# CPU.net
KiCad netlist of a schematic drawn in Altium Designer
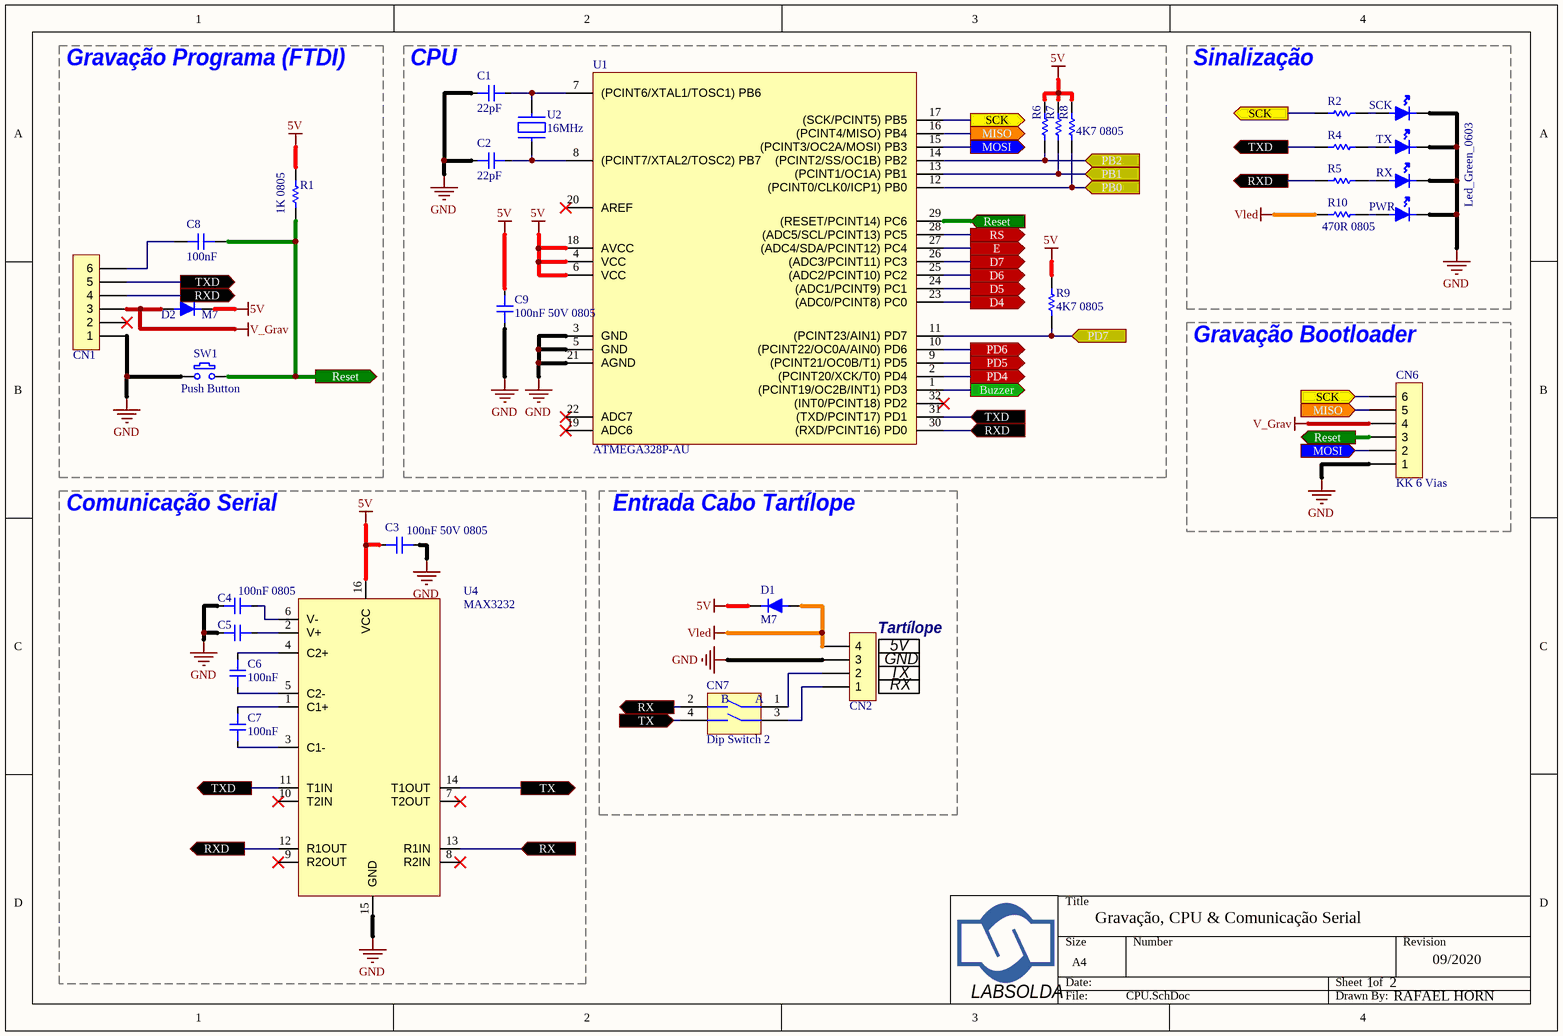
[diagram p0: CPU.SchDoc]

(export (version "E")
  (design (tool "Eeschema 10.0.6"))
  (components
    (comp (ref "C1")
      (value "22pF")
      (footprint "100nF 0805")
      (description "Capacitor 0805 100nF 16V")
      (libsource (lib "Capacitor_SMD") (part "100nF 16V 0805"))
    )
    (comp (ref "C2")
      (value "22pF")
      (footprint "100nF 0805")
      (description "Capacitor 0805 100nF 16V")
      (libsource (lib "Capacitor_SMD") (part "100nF 16V 0805"))
    )
    (comp (ref "C3")
      (value "100nF 50V 0805")
      (footprint "100nF 0805")
      (description "Capacitor 0805 100nF 16V")
      (libsource (lib "Capacitor_SMD") (part "100nF 16V 0805"))
    )
    (comp (ref "C4")
      (value "100nF 50V 0805")
      (footprint "100nF 0805")
      (description "Capacitor 0805 100nF 16V")
      (libsource (lib "Capacitor_SMD") (part "100nF 16V 0805"))
    )
    (comp (ref "C5")
      (value "100nF 0805")
      (footprint "100nF 0805")
      (description "Capacitor 0805 100nF 16V")
      (libsource (lib "Capacitor_SMD") (part "100nF 16V 0805"))
    )
    (comp (ref "C6")
      (value "100nF")
      (footprint "100nF 0805")
      (description "Capacitor 0805 100nF 16V")
      (libsource (lib "Capacitor_SMD") (part "100nF 16V 0805"))
    )
    (comp (ref "C7")
      (value "100nF")
      (footprint "100nF 0805")
      (description "Capacitor 0805 100nF 16V")
      (libsource (lib "Capacitor_SMD") (part "100nF 16V 0805"))
    )
    (comp (ref "C8")
      (value "100nF")
      (footprint "5mm film")
      (description "FILM CAPACITORS 100nF 63V")
      (libsource (lib "Capacitors_PTH") (part "100nF 63V"))
    )
    (comp (ref "C9")
      (value "100nF 50V 0805")
      (footprint "100nF 0805")
      (description "Capacitor 0805 100nF 16V")
      (libsource (lib "Capacitor_SMD") (part "100nF 16V 0805"))
    )
    (comp (ref "CN1")
      (value "Barra Pinos M")
      (footprint "Barra Pino M 6")
      (description "Barra Pino Macho 6 Vias 2.54mm")
      (libsource (lib "Conectores") (part "Barra Pino M 6"))
    )
    (comp (ref "CN2")
      (value "STLZ 4 Vias")
      (footprint "STLZ 4 5.08mm")
      (description "Conector Socket STLZ 4 Vias 5.08mm")
      (libsource (lib "Conectores") (part "STLZ 4 Vias"))
    )
    (comp (ref "CN6")
      (value "KK 6 Vias")
      (footprint "KK_6W_.100")
      (description "Conector Placa KK 6 Vias 2.54mm")
      (libsource (lib "Conectores") (part "KK 6 Vias"))
    )
    (comp (ref "CN7")
      (value "Dip Switch 2")
      (footprint "DIP_SWITCH_2")
      (description "DIP Switches / SIP Switches Dip switch Slide Type")
      (fields (field (name "PARTNUMBER") "NDSR-02V") (field (name "MANUFACTURER") "Diptronics"))
      (libsource (lib "Contatos") (part "Dip Switch 2 Vias"))
    )
    (comp (ref "D1")
      (value "M7")
      (footprint "DO-214AC SMA")
      (description "1A Rectifier Diodes")
      (libsource (lib "Diodo_SMD") (part "M7"))
    )
    (comp (ref "D2")
      (value "M7")
      (footprint "DO-214AC SMA")
      (description "1A Rectifier Diodes")
      (libsource (lib "Diodo_SMD") (part "M7"))
    )
    (comp (ref "PWR")
      (value "Green_0603")
      (footprint "Green Led 0603")
      (description "LED GREEN CLEAR 0603 SMD PN 150060VS75000")
      (libsource (lib "Leds_Lib") (part "Green 0603"))
    )
    (comp (ref "R1")
      (value "1K 0805")
      (footprint "0805 - 1K 1%")
      (description "Resistor SMD 0805 1K")
      (libsource (lib "Resistor_SMD") (part "1K - 0805"))
    )
    (comp (ref "R2")
      (value "470R 0805")
      (footprint "0805 - 470R 1%")
      (description "Resistor SMD 0805 470R")
      (libsource (lib "Resistor_SMD") (part "470R - 0805"))
    )
    (comp (ref "R4")
      (value "470R 0805")
      (footprint "0805 - 470R 1%")
      (description "Resistor SMD 0805 470R")
      (libsource (lib "Resistor_SMD") (part "470R - 0805"))
    )
    (comp (ref "R5")
      (value "470R 0805")
      (footprint "0805 - 470R 1%")
      (description "Resistor SMD 0805 470R")
      (libsource (lib "Resistor_SMD") (part "470R - 0805"))
    )
    (comp (ref "R6")
      (value "4K7")
      (footprint "0805 - 2k7 1%")
      (description "Resistor SMD 0805 2K7")
      (libsource (lib "Resistor_SMD") (part "2K7 - 0805"))
    )
    (comp (ref "R7")
      (value "4K7")
      (footprint "0805 - 2k7 1%")
      (description "Resistor SMD 0805 2K7")
      (libsource (lib "Resistor_SMD") (part "2K7 - 0805"))
    )
    (comp (ref "R8")
      (value "4K7 0805")
      (footprint "0805 - 2k7 1%")
      (description "Resistor SMD 0805 2K7")
      (libsource (lib "Resistor_SMD") (part "2K7 - 0805"))
    )
    (comp (ref "R9")
      (value "4K7 0805")
      (footprint "0805 - 2k7 1%")
      (description "Resistor SMD 0805 2K7")
      (libsource (lib "Resistor_SMD") (part "2K7 - 0805"))
    )
    (comp (ref "R10")
      (value "470R 0805")
      (footprint "0805 - 470R 1%")
      (description "Resistor SMD 0805 470R")
      (libsource (lib "Resistor_SMD") (part "470R - 0805"))
    )
    (comp (ref "RX")
      (value "Green_0603")
      (footprint "Green Led 0603")
      (description "LED GREEN CLEAR 0603 SMD PN 150060VS75000")
      (libsource (lib "Leds_Lib") (part "Green 0603"))
    )
    (comp (ref "SCK")
      (value "Led_Green_0603")
      (footprint "Green Led 0603")
      (description "LED GREEN CLEAR 0603 SMD PN 150060VS75000")
      (libsource (lib "Leds_Lib") (part "Green 0603"))
    )
    (comp (ref "SW1")
      (value "Push Button")
      (footprint "Chave Tactil 6x6x5")
      (description "Chave Tactil 4 terminais 6x6x5mm - KFC-A06")
      (libsource (lib "Contatos") (part "Push Button"))
    )
    (comp (ref "TX")
      (value "Green_0603")
      (footprint "Green Led 0603")
      (description "LED GREEN CLEAR 0603 SMD PN 150060VS75000")
      (libsource (lib "Leds_Lib") (part "Green 0603"))
    )
    (comp (ref "U1")
      (value "ATMEGA328P-AU")
      (footprint "LQFP-32")
      (description "8-bit AVR Microcontroller with 32K Bytes In-System  Programmable Flash")
      (libsource (lib "CI's") (part "ATMEGA328P"))
    )
    (comp (ref "U2")
      (value "16MHz")
      (footprint "HC49")
      (description "16MHZ OSCILATOR CRYSTAL")
      (libsource (lib "CI's") (part "Crystal 16MHz"))
    )
    (comp (ref "U4")
      (value "MAX3232")
      (footprint "DIP16-300(100)")
      (description "MAX3232 3-V to 5.5-V Multichannel RS-232 Line Driver/Receiver  With ±15-kV ESD Protection")
      (libsource (lib "CI's") (part "MAX3232"))
    )
  )
  (nets
    (net (code "1") (name "/Buzzer") (class "Default")
      (node (ref "U1") (pin "1") (pinfunction "(PCINT19/OC2B/INT1)_PD3_1") (pintype "passive"))
    )
    (net (code "2") (name "/D4") (class "Default")
      (node (ref "U1") (pin "23") (pinfunction "(ADC0/PCINT8)_PC0_23") (pintype "passive"))
    )
    (net (code "3") (name "/D5") (class "Default")
      (node (ref "U1") (pin "24") (pinfunction "(ADC1/PCINT9)_PC1_24") (pintype "passive"))
    )
    (net (code "4") (name "/D6") (class "Default")
      (node (ref "U1") (pin "25") (pinfunction "(ADC2/PCINT10)_PC2_25") (pintype "passive"))
    )
    (net (code "5") (name "/D7") (class "Default")
      (node (ref "U1") (pin "26") (pinfunction "(ADC3/PCINT11)_PC3_26") (pintype "passive"))
    )
    (net (code "6") (name "/E") (class "Default")
      (node (ref "U1") (pin "27") (pinfunction "(ADC4/SDA/PCINT12)_PC4_27") (pintype "passive"))
    )
    (net (code "7") (name "/MISO") (class "Default")
      (node (ref "CN6") (pin "5") (pinfunction "5_5") (pintype "passive"))
      (node (ref "U1") (pin "16") (pinfunction "(PCINT4/MISO)_PB4_16") (pintype "passive"))
    )
    (net (code "8") (name "/MOSI") (class "Default")
      (node (ref "CN6") (pin "2") (pinfunction "2_2") (pintype "passive"))
      (node (ref "U1") (pin "15") (pinfunction "(PCINT3/OC2A/MOSI)_PB3_15") (pintype "passive"))
    )
    (net (code "9") (name "/PB0") (class "Default")
      (node (ref "R8") (pin "1") (pinfunction "1_1") (pintype "passive"))
      (node (ref "U1") (pin "12") (pinfunction "(PCINT0/CLK0/ICP1)_PB0_12") (pintype "passive"))
    )
    (net (code "10") (name "/PB1") (class "Default")
      (node (ref "R7") (pin "1") (pinfunction "1_1") (pintype "passive"))
      (node (ref "U1") (pin "13") (pinfunction "(PCINT1/OC1A)_PB1_13") (pintype "passive"))
    )
    (net (code "11") (name "/PB2") (class "Default")
      (node (ref "R6") (pin "1") (pinfunction "1_1") (pintype "passive"))
      (node (ref "U1") (pin "14") (pinfunction "(PCINT2/SS/OC1B)_PB2_14") (pintype "passive"))
    )
    (net (code "12") (name "/PD4") (class "Default")
      (node (ref "U1") (pin "2") (pinfunction "(PCINT20/XCK/T0)_PD4_2") (pintype "passive"))
    )
    (net (code "13") (name "/PD5") (class "Default")
      (node (ref "U1") (pin "9") (pinfunction "(PCINT21/OC0B/T1)_PD5_9") (pintype "passive"))
    )
    (net (code "14") (name "/PD6") (class "Default")
      (node (ref "U1") (pin "10") (pinfunction "(PCINT22/OC0A/AIN0)_PD6_10") (pintype "passive"))
    )
    (net (code "15") (name "/PD7") (class "Default")
      (node (ref "R9") (pin "1") (pinfunction "1_1") (pintype "passive"))
      (node (ref "U1") (pin "11") (pinfunction "(PCINT23/AIN1)_PD7_11") (pintype "passive"))
    )
    (net (code "16") (name "/RS") (class "Default")
      (node (ref "U1") (pin "28") (pinfunction "(ADC5/SCL/PCINT13)_PC5_28") (pintype "passive"))
    )
    (net (code "17") (name "/RX") (class "Default")
      (node (ref "CN7") (pin "2") (pinfunction "1B_2") (pintype "passive"))
      (node (ref "U4") (pin "13") (pinfunction "R1IN_13") (pintype "passive"))
    )
    (net (code "18") (name "/RXD") (class "Default")
      (node (ref "CN1") (pin "4") (pinfunction "4_4") (pintype "passive"))
      (node (ref "R5") (pin "1") (pinfunction "1_1") (pintype "passive"))
      (node (ref "U1") (pin "30") (pinfunction "(RXD/PCINT16)_PD0_30") (pintype "passive"))
      (node (ref "U4") (pin "12") (pinfunction "R1OUT_12") (pintype "passive"))
    )
    (net (code "19") (name "/Reset") (class "Default")
      (node (ref "C8") (pin "2") (pinfunction "2_2") (pintype "passive"))
      (node (ref "CN6") (pin "3") (pinfunction "3_3") (pintype "passive"))
      (node (ref "R1") (pin "1") (pinfunction "1_1") (pintype "passive"))
      (node (ref "SW1") (pin "2") (pinfunction "2_2") (pintype "passive"))
      (node (ref "U1") (pin "29") (pinfunction "(RESET/PCINT14)_PC6_29") (pintype "passive"))
    )
    (net (code "20") (name "/SCK") (class "Default")
      (node (ref "CN6") (pin "6") (pinfunction "6_6") (pintype "passive"))
      (node (ref "R2") (pin "1") (pinfunction "1_1") (pintype "passive"))
      (node (ref "U1") (pin "17") (pinfunction "(SCK/PCINT5)_PB5_17") (pintype "passive"))
    )
    (net (code "21") (name "/TX") (class "Default")
      (node (ref "CN7") (pin "4") (pinfunction "2B_4") (pintype "passive"))
      (node (ref "U4") (pin "14") (pinfunction "T1OUT_14") (pintype "passive"))
    )
    (net (code "22") (name "/TXD") (class "Default")
      (node (ref "CN1") (pin "5") (pinfunction "5_5") (pintype "passive"))
      (node (ref "R4") (pin "1") (pinfunction "1_1") (pintype "passive"))
      (node (ref "U1") (pin "31") (pinfunction "(TXD/PCINT17)_PD1_31") (pintype "passive"))
      (node (ref "U4") (pin "11") (pinfunction "T1IN_11") (pintype "passive"))
    )
    (net (code "23") (name "5V") (class "Default")
      (node (ref "C3") (pin "2") (pinfunction "2_2") (pintype "passive"))
      (node (ref "C9") (pin "2") (pinfunction "2_2") (pintype "passive"))
      (node (ref "D1") (pin "K") (pinfunction "K_K") (pintype "passive"))
      (node (ref "D2") (pin "K") (pinfunction "K_K") (pintype "passive"))
      (node (ref "R1") (pin "2") (pinfunction "2_2") (pintype "passive"))
      (node (ref "R6") (pin "2") (pinfunction "2_2") (pintype "passive"))
      (node (ref "R7") (pin "2") (pinfunction "2_2") (pintype "passive"))
      (node (ref "R8") (pin "2") (pinfunction "2_2") (pintype "passive"))
      (node (ref "R9") (pin "2") (pinfunction "2_2") (pintype "passive"))
      (node (ref "U1") (pin "18") (pinfunction "AVCC_18") (pintype "passive"))
      (node (ref "U1") (pin "4") (pinfunction "VCC_4") (pintype "passive"))
      (node (ref "U1") (pin "6") (pinfunction "VCC_6") (pintype "passive"))
      (node (ref "U4") (pin "16") (pinfunction "VCC_16") (pintype "passive"))
    )
    (net (code "24") (name "GND") (class "Default")
      (node (ref "C1") (pin "1") (pinfunction "1_1") (pintype "passive"))
      (node (ref "C2") (pin "1") (pinfunction "1_1") (pintype "passive"))
      (node (ref "C3") (pin "1") (pinfunction "1_1") (pintype "passive"))
      (node (ref "C4") (pin "1") (pinfunction "1_1") (pintype "passive"))
      (node (ref "C5") (pin "1") (pinfunction "1_1") (pintype "passive"))
      (node (ref "C9") (pin "1") (pinfunction "1_1") (pintype "passive"))
      (node (ref "CN1") (pin "1") (pinfunction "1_1") (pintype "passive"))
      (node (ref "CN2") (pin "3") (pinfunction "3_3") (pintype "passive"))
      (node (ref "CN6") (pin "1") (pinfunction "1_1") (pintype "passive"))
      (node (ref "PWR") (pin "K") (pinfunction "K_K") (pintype "passive"))
      (node (ref "RX") (pin "K") (pinfunction "K_K") (pintype "passive"))
      (node (ref "SCK") (pin "K") (pinfunction "K_K") (pintype "passive"))
      (node (ref "SW1") (pin "1") (pinfunction "1_1") (pintype "passive"))
      (node (ref "TX") (pin "K") (pinfunction "K_K") (pintype "passive"))
      (node (ref "U1") (pin "21") (pinfunction "AGND_21") (pintype "passive"))
      (node (ref "U1") (pin "3") (pinfunction "GND_3") (pintype "passive"))
      (node (ref "U1") (pin "5") (pinfunction "GND_5") (pintype "passive"))
      (node (ref "U4") (pin "15") (pinfunction "GND_15") (pintype "passive"))
    )
    (net (code "25") (name "Net-(C8-Pad1)") (class "Default")
      (node (ref "C8") (pin "1") (pinfunction "1_1") (pintype "passive"))
      (node (ref "CN1") (pin "6") (pinfunction "6_6") (pintype "passive"))
    )
    (net (code "26") (name "Net-(CN7-1A)") (class "Default")
      (node (ref "CN2") (pin "2") (pinfunction "2_2") (pintype "passive"))
      (node (ref "CN7") (pin "1") (pinfunction "1A_1") (pintype "passive"))
    )
    (net (code "27") (name "Net-(CN7-2A)") (class "Default")
      (node (ref "CN2") (pin "1") (pinfunction "1_1") (pintype "passive"))
      (node (ref "CN7") (pin "3") (pinfunction "2A_3") (pintype "passive"))
    )
    (net (code "28") (name "Net-(PWR-PadA)") (class "Default")
      (node (ref "PWR") (pin "A") (pinfunction "A_A") (pintype "passive"))
      (node (ref "R10") (pin "2") (pinfunction "2_2") (pintype "passive"))
    )
    (net (code "29") (name "Net-(R2-Pad2)") (class "Default")
      (node (ref "R2") (pin "2") (pinfunction "2_2") (pintype "passive"))
      (node (ref "SCK") (pin "A") (pinfunction "A_A") (pintype "passive"))
    )
    (net (code "30") (name "Net-(R4-Pad2)") (class "Default")
      (node (ref "R4") (pin "2") (pinfunction "2_2") (pintype "passive"))
      (node (ref "TX") (pin "A") (pinfunction "A_A") (pintype "passive"))
    )
    (net (code "31") (name "Net-(R5-Pad2)") (class "Default")
      (node (ref "R5") (pin "2") (pinfunction "2_2") (pintype "passive"))
      (node (ref "RX") (pin "A") (pinfunction "A_A") (pintype "passive"))
    )
    (net (code "32") (name "Net-(U1-(PCINT6{slash}XTAL1{slash}TOSC1)_PB6)") (class "Default")
      (node (ref "C1") (pin "2") (pinfunction "2_2") (pintype "passive"))
      (node (ref "U1") (pin "7") (pinfunction "(PCINT6/XTAL1/TOSC1)_PB6_7") (pintype "passive"))
      (node (ref "U2") (pin "1") (pinfunction "1_1") (pintype "passive"))
    )
    (net (code "33") (name "Net-(U1-(PCINT7{slash}XTAL2{slash}TOSC2)_PB7)") (class "Default")
      (node (ref "C2") (pin "2") (pinfunction "2_2") (pintype "passive"))
      (node (ref "U1") (pin "8") (pinfunction "(PCINT7/XTAL2/TOSC2)_PB7_8") (pintype "passive"))
      (node (ref "U2") (pin "2") (pinfunction "2_2") (pintype "passive"))
    )
    (net (code "34") (name "Net-(U4-C1+)") (class "Default")
      (node (ref "C7") (pin "2") (pinfunction "2_2") (pintype "passive"))
      (node (ref "U4") (pin "1") (pinfunction "C1+_1") (pintype "passive"))
    )
    (net (code "35") (name "Net-(U4-C1-)") (class "Default")
      (node (ref "C7") (pin "1") (pinfunction "1_1") (pintype "passive"))
      (node (ref "U4") (pin "3") (pinfunction "C1-_3") (pintype "passive"))
    )
    (net (code "36") (name "Net-(U4-C2+)") (class "Default")
      (node (ref "C6") (pin "2") (pinfunction "2_2") (pintype "passive"))
      (node (ref "U4") (pin "4") (pinfunction "C2+_4") (pintype "passive"))
    )
    (net (code "37") (name "Net-(U4-C2-)") (class "Default")
      (node (ref "C6") (pin "1") (pinfunction "1_1") (pintype "passive"))
      (node (ref "U4") (pin "5") (pinfunction "C2-_5") (pintype "passive"))
    )
    (net (code "38") (name "Net-(U4-V+)") (class "Default")
      (node (ref "C5") (pin "2") (pinfunction "2_2") (pintype "passive"))
      (node (ref "U4") (pin "2") (pinfunction "V+_2") (pintype "passive"))
    )
    (net (code "39") (name "Net-(U4-V-)") (class "Default")
      (node (ref "C4") (pin "2") (pinfunction "2_2") (pintype "passive"))
      (node (ref "U4") (pin "6") (pinfunction "V-_6") (pintype "passive"))
    )
    (net (code "40") (name "V_Grav") (class "Default")
      (node (ref "CN1") (pin "3") (pinfunction "3_3") (pintype "passive"))
      (node (ref "CN6") (pin "4") (pinfunction "4_4") (pintype "passive"))
      (node (ref "D2") (pin "A") (pinfunction "A_A") (pintype "passive"))
    )
    (net (code "41") (name "Vled") (class "Default")
      (node (ref "CN2") (pin "4") (pinfunction "4_4") (pintype "passive"))
      (node (ref "D1") (pin "A") (pinfunction "A_A") (pintype "passive"))
      (node (ref "R10") (pin "1") (pinfunction "1_1") (pintype "passive"))
    )
    (net (code "42") (name "unconnected-(CN1-Pad2)") (class "Default")
      (node (ref "CN1") (pin "2") (pinfunction "2_2") (pintype "passive+no_connect"))
    )
    (net (code "43") (name "unconnected-(U1-(INT0{slash}PCINT18)_PD2-Pad32)") (class "Default")
      (node (ref "U1") (pin "32") (pinfunction "(INT0/PCINT18)_PD2_32") (pintype "passive+no_connect"))
    )
    (net (code "44") (name "unconnected-(U1-ADC6-Pad19)") (class "Default")
      (node (ref "U1") (pin "19") (pinfunction "ADC6_19") (pintype "passive+no_connect"))
    )
    (net (code "45") (name "unconnected-(U1-ADC7-Pad22)") (class "Default")
      (node (ref "U1") (pin "22") (pinfunction "ADC7_22") (pintype "passive+no_connect"))
    )
    (net (code "46") (name "unconnected-(U1-AREF-Pad20)") (class "Default")
      (node (ref "U1") (pin "20") (pinfunction "AREF_20") (pintype "passive+no_connect"))
    )
    (net (code "47") (name "unconnected-(U4-R2IN-Pad8)") (class "Default")
      (node (ref "U4") (pin "8") (pinfunction "R2IN_8") (pintype "passive+no_connect"))
    )
    (net (code "48") (name "unconnected-(U4-R2OUT-Pad9)") (class "Default")
      (node (ref "U4") (pin "9") (pinfunction "R2OUT_9") (pintype "passive+no_connect"))
    )
    (net (code "49") (name "unconnected-(U4-T2IN-Pad10)") (class "Default")
      (node (ref "U4") (pin "10") (pinfunction "T2IN_10") (pintype "passive+no_connect"))
    )
    (net (code "50") (name "unconnected-(U4-T2OUT-Pad7)") (class "Default")
      (node (ref "U4") (pin "7") (pinfunction "T2OUT_7") (pintype "passive+no_connect"))
    )
  )
)
